# 07_SERIAL-USB.net
KiCad netlist of a schematic drawn in Altium Designer
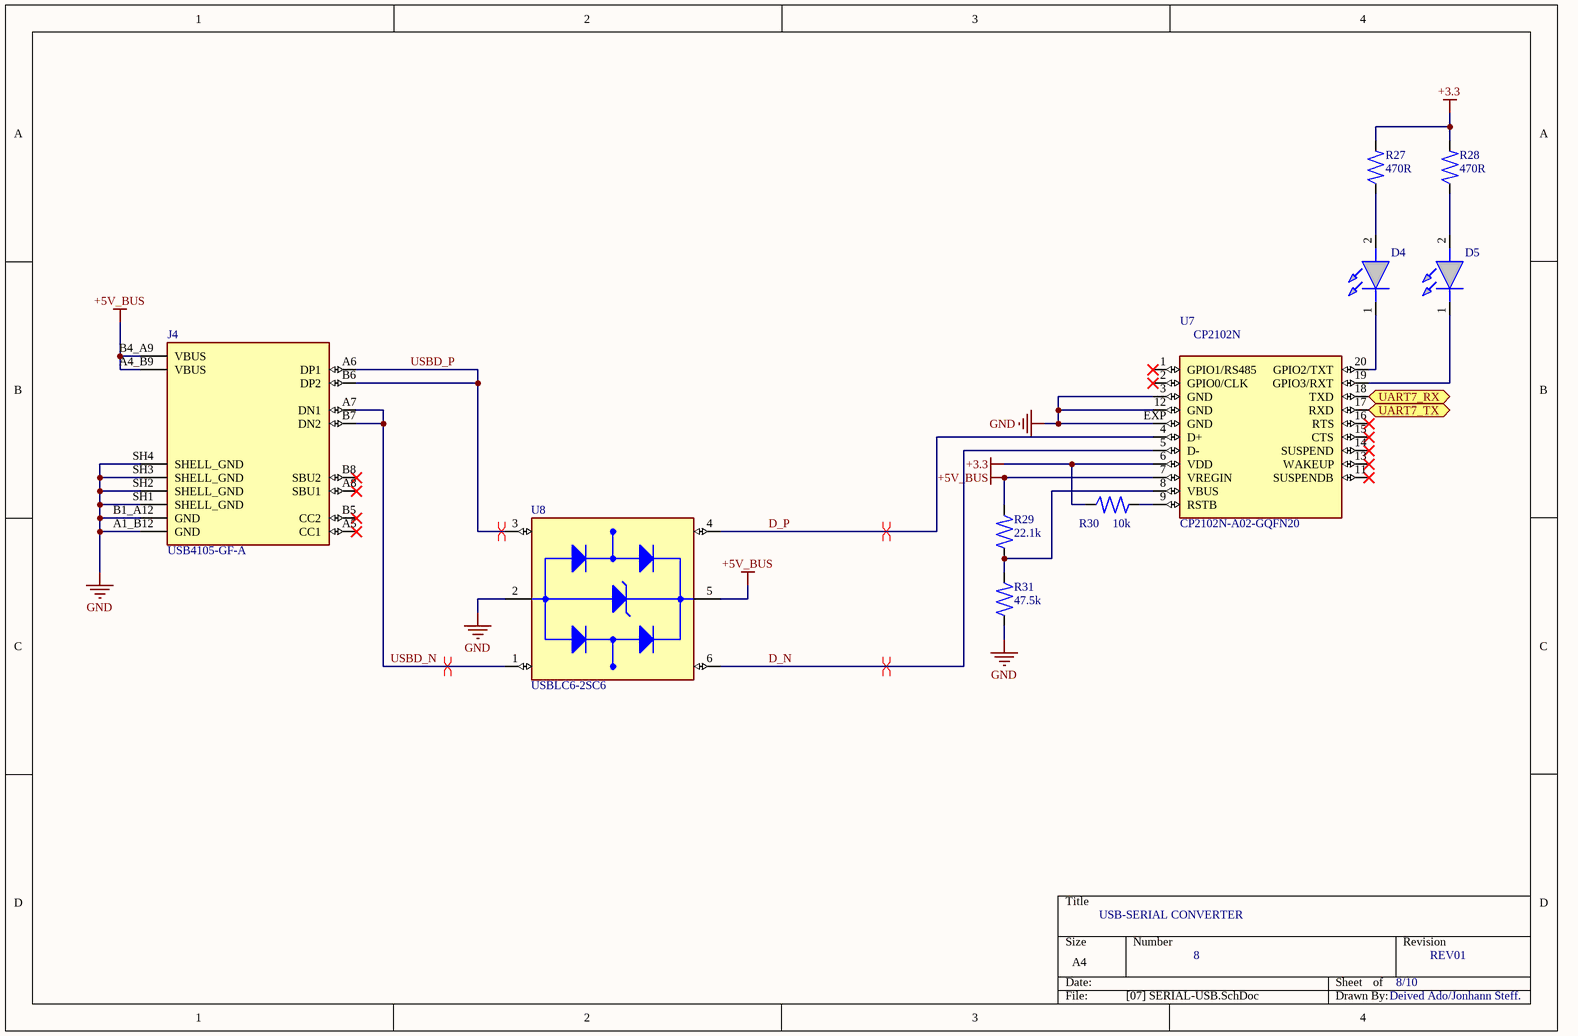
[diagram p0: [07] SERIAL-USB.SchDoc]

(export (version "E")
  (design (tool "Eeschema 10.0.6"))
  (components
    (comp (ref "D4")
      (value "LED GREEN SMD")
      (footprint "LED 0805")
      (description "LED Green 0805 Rectangular")
      (fields (field (name "MFR. PART #") "15008GS75000") (field (name "MANUFACTURER") "Wurth Elektronik"))
      (libsource (lib "Integrated_Library_IST") (part "LED GREEN SMD"))
    )
    (comp (ref "D5")
      (value "LED GREEN SMD")
      (footprint "LED 0805")
      (description "LED Green 0805 Rectangular")
      (fields (field (name "MFR. PART #") "15008GS75000") (field (name "MANUFACTURER") "Wurth Elektronik"))
      (libsource (lib "Integrated_Library_IST") (part "LED GREEN SMD"))
    )
    (comp (ref "J4")
      (value "USB4105-GF-A")
      (footprint "GCT_USB4105-GF-A")
      (fields (field (name "MF") "GCT"))
      (libsource (lib "Integrated_Library_IST") (part "USB4105-GF-A"))
    )
    (comp (ref "R27")
      (value "470R")
      (footprint "RES_0603")
      (description "Generic Resistor symbol")
      (libsource (lib "Integrated_Library_IST") (part "R_Small"))
    )
    (comp (ref "R28")
      (value "470R")
      (footprint "RES_0603")
      (description "Generic Resistor symbol")
      (libsource (lib "Integrated_Library_IST") (part "R_Small"))
    )
    (comp (ref "R29")
      (value "22.1k")
      (footprint "RES_0603")
      (description "Generic Resistor symbol")
      (libsource (lib "Integrated_Library_IST") (part "R_Small"))
    )
    (comp (ref "R30")
      (value "10k")
      (footprint "RES_0603")
      (description "Generic Resistor symbol")
      (libsource (lib "Integrated_Library_IST") (part "R_Small"))
    )
    (comp (ref "R31")
      (value "47.5k")
      (footprint "RES_0603")
      (description "Generic Resistor symbol")
      (libsource (lib "Integrated_Library_IST") (part "R_Small"))
    )
    (comp (ref "U7")
      (value "CP2102N-A02-GQFN20")
      (footprint "WFQFN-20")
      (description "USB Bridge, USB to UART USB 2.0 UART Interface 20-QFN (3x3)")
      (fields (field (name "MF") "Silicon Labs"))
      (libsource (lib "Integrated_Library_IST") (part "CP2102N-A02-GQFN20"))
    )
    (comp (ref "U8")
      (value "USBLC6-2SC6")
      (footprint "SOT95P280X145-6N")
      (description "17V Clamp 5A (8/20Âµs) Ipp Tvs Diode Surface Mount SOT-23-6")
      (fields (field (name "MF") "STMicroelectronics"))
      (libsource (lib "Integrated_Library - Rev1-DESKTOP-6DENAEC") (part "USBLC6-2SC6"))
    )
  )
  (nets
    (net (code "1") (name "+3.3") (class "Default")
      (node (ref "R27") (pin "1") (pinfunction "1_1") (pintype "passive"))
      (node (ref "R28") (pin "1") (pinfunction "1_1") (pintype "passive"))
      (node (ref "R30") (pin "2") (pinfunction "2_2") (pintype "passive"))
      (node (ref "U7") (pin "6") (pinfunction "VDD_6") (pintype "bidirectional"))
    )
    (net (code "2") (name "+5V_BUS") (class "Default")
      (node (ref "J4") (pin "A4_B9") (pinfunction "VBUS_A4_B9") (pintype "power_in"))
      (node (ref "J4") (pin "B4_A9") (pinfunction "VBUS_B4_A9") (pintype "power_in"))
      (node (ref "R29") (pin "2") (pinfunction "2_2") (pintype "passive"))
      (node (ref "U7") (pin "7") (pinfunction "VREGIN_7") (pintype "bidirectional"))
      (node (ref "U8") (pin "5") (pinfunction "VBUS_5") (pintype "power_in"))
    )
    (net (code "3") (name "/D_N") (class "Default")
      (node (ref "U7") (pin "5") (pinfunction "D-_5") (pintype "bidirectional"))
      (node (ref "U8") (pin "6") (pinfunction "I/O1_OUT_6") (pintype "bidirectional"))
    )
    (net (code "4") (name "/D_P") (class "Default")
      (node (ref "U7") (pin "4") (pinfunction "D+_4") (pintype "bidirectional"))
      (node (ref "U8") (pin "4") (pinfunction "I/O2_OUT_4") (pintype "bidirectional"))
    )
    (net (code "5") (name "/UART7_RX") (class "Default")
      (node (ref "U7") (pin "18") (pinfunction "TXD_18") (pintype "bidirectional"))
    )
    (net (code "6") (name "/UART7_TX") (class "Default")
      (node (ref "U7") (pin "17") (pinfunction "RXD_17") (pintype "bidirectional"))
    )
    (net (code "7") (name "/USBD_N") (class "Default")
      (node (ref "J4") (pin "A7") (pinfunction "DN1_A7") (pintype "bidirectional"))
      (node (ref "J4") (pin "B7") (pinfunction "DN2_B7") (pintype "bidirectional"))
      (node (ref "U8") (pin "1") (pinfunction "I/O1_IN_1") (pintype "bidirectional"))
    )
    (net (code "8") (name "/USBD_P") (class "Default")
      (node (ref "J4") (pin "A6") (pinfunction "DP1_A6") (pintype "bidirectional"))
      (node (ref "J4") (pin "B6") (pinfunction "DP2_B6") (pintype "bidirectional"))
      (node (ref "U8") (pin "3") (pinfunction "I/O2_IN_3") (pintype "bidirectional"))
    )
    (net (code "9") (name "GND") (class "Default")
      (node (ref "J4") (pin "A1_B12") (pinfunction "GND_A1_B12") (pintype "power_in"))
      (node (ref "J4") (pin "B1_A12") (pinfunction "GND_B1_A12") (pintype "power_in"))
      (node (ref "J4") (pin "SH1") (pinfunction "SHELL_GND_SH1") (pintype "power_in"))
      (node (ref "J4") (pin "SH2") (pinfunction "SHELL_GND_SH2") (pintype "power_in"))
      (node (ref "J4") (pin "SH3") (pinfunction "SHELL_GND_SH3") (pintype "power_in"))
      (node (ref "J4") (pin "SH4") (pinfunction "SHELL_GND_SH4") (pintype "power_in"))
      (node (ref "R31") (pin "1") (pinfunction "1_1") (pintype "passive"))
      (node (ref "U7") (pin "12") (pinfunction "GND_12") (pintype "bidirectional"))
      (node (ref "U7") (pin "3") (pinfunction "GND_3") (pintype "bidirectional"))
      (node (ref "U7") (pin "EXP") (pinfunction "GND_EXP") (pintype "bidirectional"))
      (node (ref "U8") (pin "2") (pinfunction "GND_2") (pintype "power_in"))
    )
    (net (code "10") (name "Net-(D4-A)") (class "Default")
      (node (ref "D4") (pin "2") (pinfunction "A_2") (pintype "passive"))
      (node (ref "R27") (pin "2") (pinfunction "2_2") (pintype "passive"))
    )
    (net (code "11") (name "Net-(D4-K)") (class "Default")
      (node (ref "D4") (pin "1") (pinfunction "K_1") (pintype "passive"))
      (node (ref "U7") (pin "20") (pinfunction "GPIO2/TXT_20") (pintype "bidirectional"))
    )
    (net (code "12") (name "Net-(D5-A)") (class "Default")
      (node (ref "D5") (pin "2") (pinfunction "A_2") (pintype "passive"))
      (node (ref "R28") (pin "2") (pinfunction "2_2") (pintype "passive"))
    )
    (net (code "13") (name "Net-(D5-K)") (class "Default")
      (node (ref "D5") (pin "1") (pinfunction "K_1") (pintype "passive"))
      (node (ref "U7") (pin "19") (pinfunction "GPIO3/RXT_19") (pintype "bidirectional"))
    )
    (net (code "14") (name "Net-(U7-RSTB)") (class "Default")
      (node (ref "R30") (pin "1") (pinfunction "1_1") (pintype "passive"))
      (node (ref "U7") (pin "9") (pinfunction "RSTB_9") (pintype "bidirectional"))
    )
    (net (code "15") (name "Net-(U7-VBUS)") (class "Default")
      (node (ref "R29") (pin "1") (pinfunction "1_1") (pintype "passive"))
      (node (ref "R31") (pin "2") (pinfunction "2_2") (pintype "passive"))
      (node (ref "U7") (pin "8") (pinfunction "VBUS_8") (pintype "bidirectional"))
    )
    (net (code "16") (name "unconnected-(J4-CC1-PadA5)") (class "Default")
      (node (ref "J4") (pin "A5") (pinfunction "CC1_A5") (pintype "bidirectional+no_connect"))
    )
    (net (code "17") (name "unconnected-(J4-CC2-PadB5)") (class "Default")
      (node (ref "J4") (pin "B5") (pinfunction "CC2_B5") (pintype "bidirectional+no_connect"))
    )
    (net (code "18") (name "unconnected-(J4-SBU1-PadA8)") (class "Default")
      (node (ref "J4") (pin "A8") (pinfunction "SBU1_A8") (pintype "bidirectional+no_connect"))
    )
    (net (code "19") (name "unconnected-(J4-SBU2-PadB8)") (class "Default")
      (node (ref "J4") (pin "B8") (pinfunction "SBU2_B8") (pintype "bidirectional+no_connect"))
    )
    (net (code "20") (name "unconnected-(U7-CTS-Pad15)") (class "Default")
      (node (ref "U7") (pin "15") (pinfunction "CTS_15") (pintype "bidirectional+no_connect"))
    )
    (net (code "21") (name "unconnected-(U7-GPIO0{slash}CLK-Pad2)") (class "Default")
      (node (ref "U7") (pin "2") (pinfunction "GPIO0/CLK_2") (pintype "bidirectional+no_connect"))
    )
    (net (code "22") (name "unconnected-(U7-GPIO1{slash}RS485-Pad1)") (class "Default")
      (node (ref "U7") (pin "1") (pinfunction "GPIO1/RS485_1") (pintype "bidirectional+no_connect"))
    )
    (net (code "23") (name "unconnected-(U7-RTS-Pad16)") (class "Default")
      (node (ref "U7") (pin "16") (pinfunction "RTS_16") (pintype "bidirectional+no_connect"))
    )
    (net (code "24") (name "unconnected-(U7-SUSPEND-Pad14)") (class "Default")
      (node (ref "U7") (pin "14") (pinfunction "SUSPEND_14") (pintype "bidirectional+no_connect"))
    )
    (net (code "25") (name "unconnected-(U7-SUSPENDB-Pad11)") (class "Default")
      (node (ref "U7") (pin "11") (pinfunction "SUSPENDB_11") (pintype "bidirectional+no_connect"))
    )
    (net (code "26") (name "unconnected-(U7-WAKEUP-Pad13)") (class "Default")
      (node (ref "U7") (pin "13") (pinfunction "WAKEUP_13") (pintype "bidirectional+no_connect"))
    )
  )
)
